# SingleInputThreeOutputConnection.net
KiCad netlist of a schematic drawn in EAGLE
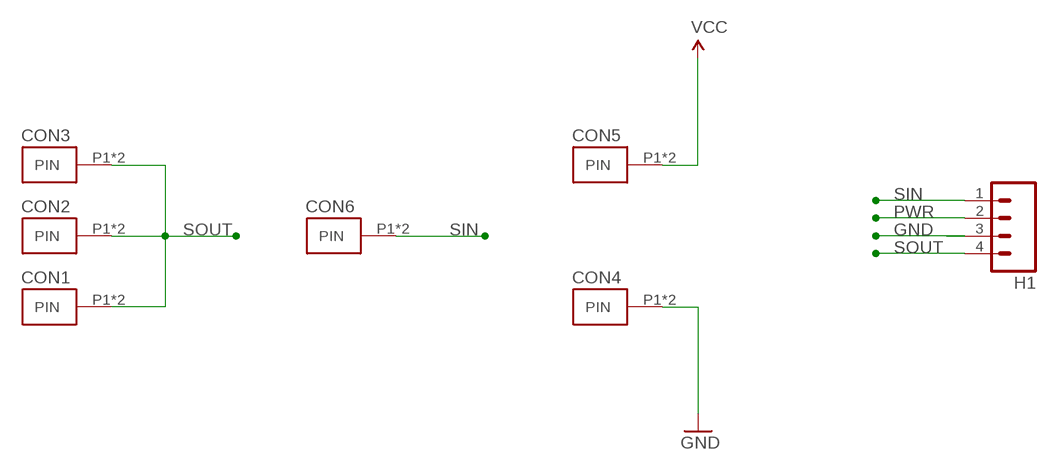
[diagram p0: schematic, sheet 1]

(export (version "E")
  (design (tool "Eeschema 10.0.6"))
  (components
    (comp (ref "CON1")
      (value "SHIELD_FINGER0820")
      (footprint "eagle-import:SHIELD_FINGER_PKG")
      (libsource (lib "eagle-import") (part "SHIELD_FINGER0820"))
    )
    (comp (ref "CON2")
      (value "SHIELD_FINGER0820")
      (footprint "eagle-import:SHIELD_FINGER_PKG")
      (libsource (lib "eagle-import") (part "SHIELD_FINGER0820"))
    )
    (comp (ref "CON3")
      (value "SHIELD_FINGER0820")
      (footprint "eagle-import:SHIELD_FINGER_PKG")
      (libsource (lib "eagle-import") (part "SHIELD_FINGER0820"))
    )
    (comp (ref "CON4")
      (value "SHIELD_FINGER0820")
      (footprint "eagle-import:SHIELD_FINGER_PKG")
      (libsource (lib "eagle-import") (part "SHIELD_FINGER0820"))
    )
    (comp (ref "CON5")
      (value "SHIELD_FINGER0820")
      (footprint "eagle-import:SHIELD_FINGER_PKG")
      (libsource (lib "eagle-import") (part "SHIELD_FINGER0820"))
    )
    (comp (ref "CON6")
      (value "SHIELD_FINGER0820")
      (footprint "eagle-import:SHIELD_FINGER_PKG")
      (libsource (lib "eagle-import") (part "SHIELD_FINGER0820"))
    )
    (comp (ref "H1")
      (value "M04")
      (footprint "eagle-import:1X04_NO_HOLES")
      (libsource (lib "eagle-import") (part "M04"))
    )
  )
  (nets
    (net (code "1") (name "/SIN") (class "Default")
      (node (ref "CON6") (pin "P1") (pinfunction "PIN_P1") (pintype "bidirectional"))
      (node (ref "CON6") (pin "P2") (pinfunction "PIN_P2") (pintype "bidirectional"))
      (node (ref "H1") (pin "1") (pinfunction "1_1") (pintype "passive"))
    )
    (net (code "2") (name "/SOUT") (class "Default")
      (node (ref "CON1") (pin "P1") (pinfunction "PIN_P1") (pintype "bidirectional"))
      (node (ref "CON1") (pin "P2") (pinfunction "PIN_P2") (pintype "bidirectional"))
      (node (ref "CON2") (pin "P1") (pinfunction "PIN_P1") (pintype "bidirectional"))
      (node (ref "CON2") (pin "P2") (pinfunction "PIN_P2") (pintype "bidirectional"))
      (node (ref "CON3") (pin "P1") (pinfunction "PIN_P1") (pintype "bidirectional"))
      (node (ref "CON3") (pin "P2") (pinfunction "PIN_P2") (pintype "bidirectional"))
      (node (ref "H1") (pin "4") (pinfunction "4_4") (pintype "passive"))
    )
    (net (code "3") (name "GND") (class "Default")
      (node (ref "CON4") (pin "P1") (pinfunction "PIN_P1") (pintype "bidirectional"))
      (node (ref "CON4") (pin "P2") (pinfunction "PIN_P2") (pintype "bidirectional"))
      (node (ref "H1") (pin "3") (pinfunction "3_3") (pintype "passive"))
    )
    (net (code "4") (name "VCC") (class "Default")
      (node (ref "CON5") (pin "P1") (pinfunction "PIN_P1") (pintype "bidirectional"))
      (node (ref "CON5") (pin "P2") (pinfunction "PIN_P2") (pintype "bidirectional"))
      (node (ref "H1") (pin "2") (pinfunction "2_2") (pintype "passive"))
    )
  )
)
